# smd_missing_pulse_detector.net
KiCad netlist of a schematic drawn in EAGLE
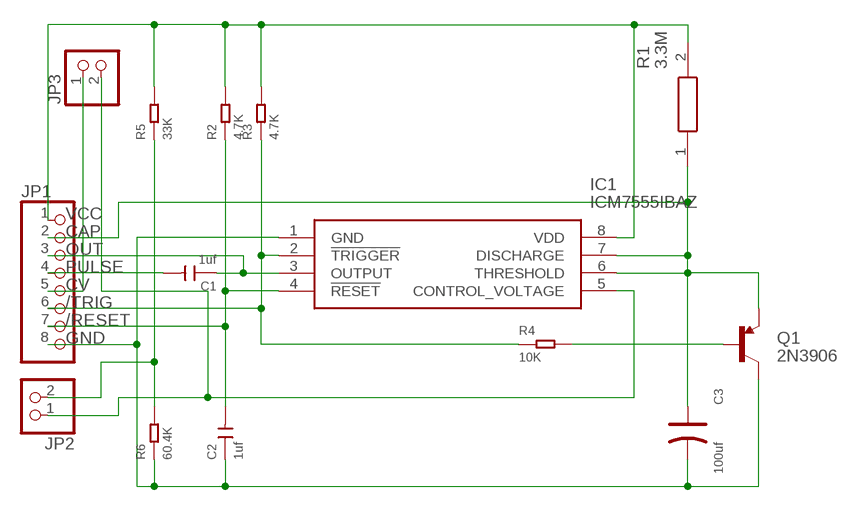
[diagram p0: schematic, sheet 1]

(export (version "E")
  (design (tool "Eeschema 10.0.6"))
  (components
    (comp (ref "C1")
      (value "1uf")
      (footprint "eagle-import:C0805")
      (fields (field (name "MPN") "CC0805KKX7R8BB105"))
      (libsource (lib "eagle-import") (part "CERAMIC-1UF-25V-10%-X7R(0805)"))
    )
    (comp (ref "C2")
      (value "1uf")
      (footprint "eagle-import:C0805")
      (fields (field (name "MPN") "CC0805KKX7R8BB105"))
      (libsource (lib "eagle-import") (part "CERAMIC-1UF-25V-10%-X7R(0805)"))
    )
    (comp (ref "C3")
      (value "100uf")
      (footprint "eagle-import:AVX-B")
      (fields (field (name "MPN") "TAJB107M010#NJ"))
      (libsource (lib "eagle-import") (part "TANTALUM-SMD-100UF-10V(AVX-B)"))
    )
    (comp (ref "IC1")
      (value "ICM7555IBAZ")
      (footprint "eagle-import:SOIC127P600X175-8N")
      (fields (field (name "MOUSER_PART_NUMBER") "968-ICM7555IBAZ"))
      (libsource (lib "eagle-import") (part "ICM7555IBAZ"))
    )
    (comp (ref "JP1")
      (value "PINHD-1X8")
      (footprint "eagle-import:1X08")
      (libsource (lib "eagle-import") (part "PINHD-1X8"))
    )
    (comp (ref "JP2")
      (value "PINHD-1X2")
      (footprint "eagle-import:1X02")
      (libsource (lib "eagle-import") (part "PINHD-1X2"))
    )
    (comp (ref "JP3")
      (value "PINHD-1X2")
      (footprint "eagle-import:1X02")
      (libsource (lib "eagle-import") (part "PINHD-1X2"))
    )
    (comp (ref "Q1")
      (value "2N3906")
      (footprint "eagle-import:SOT23-3")
      (libsource (lib "eagle-import") (part "TRANSISTOR_PNPPMBT3906"))
    )
    (comp (ref "R1")
      (value "3.3M")
      (footprint "eagle-import:RESC1608X50N")
      (fields
        (field (name "ARROW_PART_NUMBER") "CRCW06033M30FKEA")
        (field (name "MOUSER_PART_NUMBER") "71-CRCW06033M30FKEA")
      )
      (libsource (lib "eagle-import") (part "CRCW06033M30FKEA"))
    )
    (comp (ref "R2")
      (value "4.7K")
      (footprint "eagle-import:R0603")
      (fields (field (name "MPN") "RC0603JR-074K7L"))
      (libsource (lib "eagle-import") (part "SMD-RES-4.7K-5%-1/10W(0603)"))
    )
    (comp (ref "R3")
      (value "4.7K")
      (footprint "eagle-import:R0603")
      (fields (field (name "MPN") "RC0603JR-074K7L"))
      (libsource (lib "eagle-import") (part "SMD-RES-4.7K-5%-1/10W(0603)"))
    )
    (comp (ref "R4")
      (value "10K")
      (footprint "eagle-import:R0603")
      (fields (field (name "MPN") "RC0603FR-0710KL"))
      (libsource (lib "eagle-import") (part "SMD-RES-10K-1%-1/10W(0603)"))
    )
    (comp (ref "R5")
      (value "33K")
      (footprint "eagle-import:R0603")
      (fields (field (name "MPN") "RC0603JR-074K7L"))
      (libsource (lib "eagle-import") (part "SMD-RES-4.7K-5%-1/10W(0603)"))
    )
    (comp (ref "R6")
      (value "60.4K")
      (footprint "eagle-import:R0603")
      (fields (field (name "MPN") "RC0603JR-074K7L"))
      (libsource (lib "eagle-import") (part "SMD-RES-4.7K-5%-1/10W(0603)"))
    )
  )
  (nets
    (net (code "1") (name "/CAP") (class "Default")
      (node (ref "C3") (pin "+") (pinfunction "+_+") (pintype "passive"))
      (node (ref "IC1") (pin "6") (pinfunction "THRESHOLD_6") (pintype "bidirectional"))
      (node (ref "IC1") (pin "7") (pinfunction "DISCHARGE_7") (pintype "bidirectional"))
      (node (ref "JP1") (pin "2") (pinfunction "2_2") (pintype "passive"))
      (node (ref "Q1") (pin "2") (pinfunction "E_2") (pintype "passive"))
      (node (ref "R1") (pin "1") (pinfunction "1_1") (pintype "bidirectional"))
    )
    (net (code "2") (name "/CV") (class "Default")
      (node (ref "IC1") (pin "5") (pinfunction "CONTROL_VOLTAGE_5") (pintype "bidirectional"))
      (node (ref "JP2") (pin "1") (pinfunction "1_1") (pintype "passive"))
      (node (ref "JP3") (pin "2") (pinfunction "2_2") (pintype "passive"))
    )
    (net (code "3") (name "/GND") (class "Default")
      (node (ref "C2") (pin "1") (pinfunction "1_1") (pintype "passive"))
      (node (ref "C3") (pin "-") (pinfunction "-_-") (pintype "passive"))
      (node (ref "IC1") (pin "1") (pinfunction "GND_1") (pintype "bidirectional"))
      (node (ref "JP1") (pin "8") (pinfunction "8_8") (pintype "passive"))
      (node (ref "Q1") (pin "3") (pinfunction "C_3") (pintype "passive"))
      (node (ref "R6") (pin "1") (pinfunction "1_1") (pintype "passive"))
    )
    (net (code "4") (name "/OUT") (class "Default")
      (node (ref "C1") (pin "1") (pinfunction "1_1") (pintype "passive"))
      (node (ref "IC1") (pin "3") (pinfunction "OUTPUT_3") (pintype "bidirectional"))
      (node (ref "JP1") (pin "3") (pinfunction "3_3") (pintype "passive"))
    )
    (net (code "5") (name "/PULSE") (class "Default")
      (node (ref "C1") (pin "2") (pinfunction "2_2") (pintype "passive"))
      (node (ref "JP1") (pin "4") (pinfunction "4_4") (pintype "passive"))
    )
    (net (code "6") (name "/VCC") (class "Default")
      (node (ref "IC1") (pin "8") (pinfunction "VDD_8") (pintype "bidirectional"))
      (node (ref "JP1") (pin "1") (pinfunction "1_1") (pintype "passive"))
      (node (ref "R1") (pin "2") (pinfunction "2_2") (pintype "bidirectional"))
      (node (ref "R2") (pin "2") (pinfunction "2_2") (pintype "passive"))
      (node (ref "R3") (pin "2") (pinfunction "2_2") (pintype "passive"))
      (node (ref "R5") (pin "2") (pinfunction "2_2") (pintype "passive"))
    )
    (net (code "7") (name "/{slash}RESET") (class "Default")
      (node (ref "C2") (pin "2") (pinfunction "2_2") (pintype "passive"))
      (node (ref "IC1") (pin "4") (pinfunction "~{RESET}_4") (pintype "bidirectional"))
      (node (ref "JP1") (pin "7") (pinfunction "7_7") (pintype "passive"))
      (node (ref "R2") (pin "1") (pinfunction "1_1") (pintype "passive"))
    )
    (net (code "8") (name "/{slash}TRIG") (class "Default")
      (node (ref "IC1") (pin "2") (pinfunction "~{TRIGGER}_2") (pintype "bidirectional"))
      (node (ref "JP1") (pin "6") (pinfunction "6_6") (pintype "passive"))
      (node (ref "R3") (pin "1") (pinfunction "1_1") (pintype "passive"))
      (node (ref "R4") (pin "1") (pinfunction "1_1") (pintype "passive"))
    )
    (net (code "9") (name "Net-(JP1-Pad5)") (class "Default")
      (node (ref "JP1") (pin "5") (pinfunction "5_5") (pintype "passive"))
      (node (ref "JP3") (pin "1") (pinfunction "1_1") (pintype "passive"))
    )
    (net (code "10") (name "Net-(JP2-Pad2)") (class "Default")
      (node (ref "JP2") (pin "2") (pinfunction "2_2") (pintype "passive"))
      (node (ref "R5") (pin "1") (pinfunction "1_1") (pintype "passive"))
      (node (ref "R6") (pin "2") (pinfunction "2_2") (pintype "passive"))
    )
    (net (code "11") (name "Net-(Q1-B)") (class "Default")
      (node (ref "Q1") (pin "1") (pinfunction "B_1") (pintype "passive"))
      (node (ref "R4") (pin "2") (pinfunction "2_2") (pintype "passive"))
    )
  )
)
